# IO2.net
KiCad netlist of a schematic drawn in Altium Designer
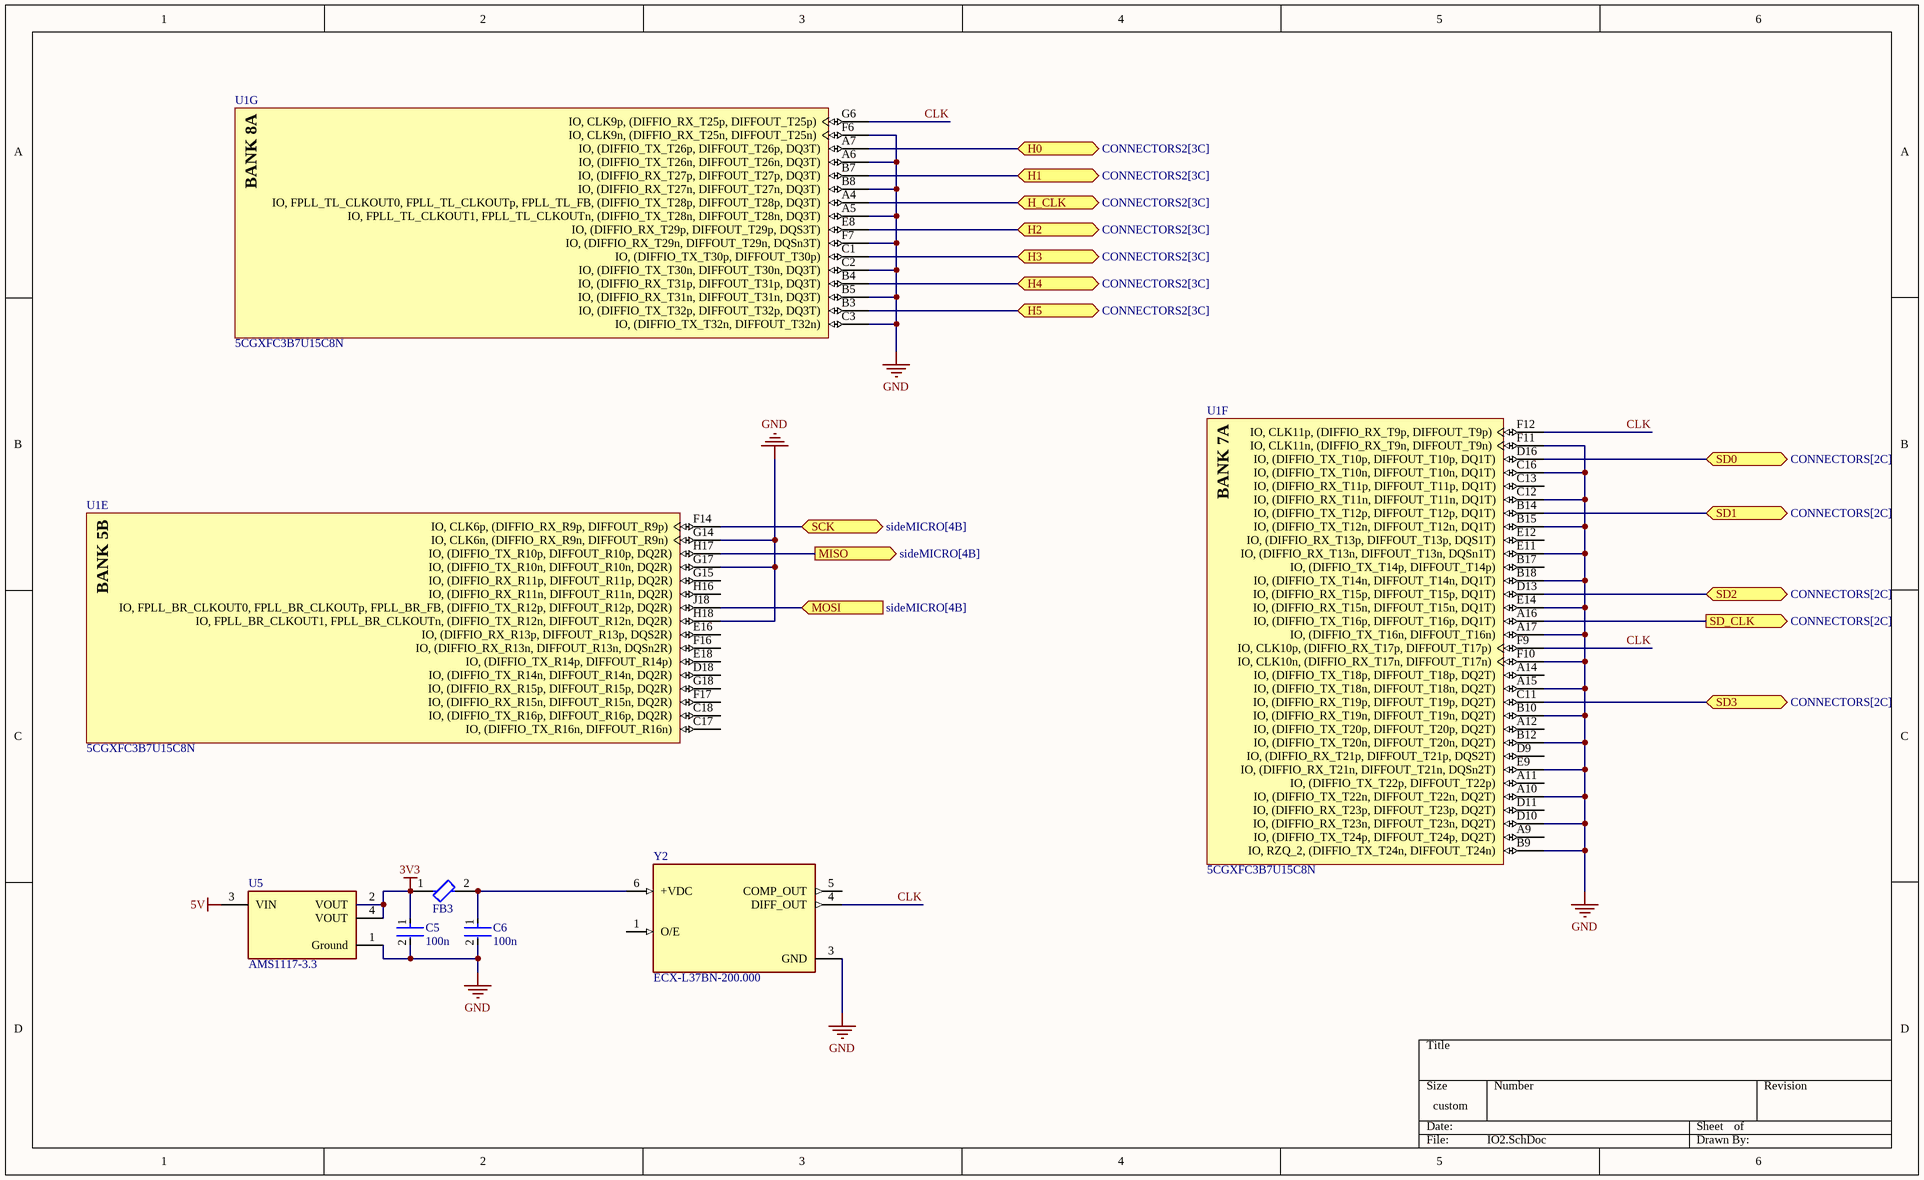
[diagram p0: IO2.SchDoc]

(export (version "E")
  (design (tool "Eeschema 10.0.6"))
  (components
    (comp (ref "C5")
      (value "100n")
      (footprint "FP-CL10-IPC_C")
      (description "Cap Ceramic 4.7uF 10V X5R ±10% Pad SMD 0603 +85°C T/R")
      (fields (field (name "TOLERANCE") "10%"))
      (libsource (lib "Altium Content Vault") (part "b4654b650e69147ec39a6b967a45e02"))
    )
    (comp (ref "C6")
      (value "100n")
      (footprint "FP-CL10-IPC_C")
      (description "Cap Ceramic 4.7uF 10V X5R ±10% Pad SMD 0603 +85°C T/R")
      (fields (field (name "TOLERANCE") "10%"))
      (libsource (lib "Altium Content Vault") (part "b4654b650e69147ec39a6b967a45e02"))
    )
    (comp (ref "FB3")
      (value "BLM18KG121TN1D")
      (footprint "FP-BLM18-0_15-t0_6-d1_2-IPC_A")
      (description "FERRITE BEAD 120 OHM 0603 1LN")
      (fields (field (name "TOLERANCE") "25%"))
      (libsource (lib "Altium Content Vault") (part "5f30dd21d616792df468990f7003faa"))
    )
    (comp (ref "U1")
      (value "5CGXFC3B7U15C8N")
      (footprint "ALTR-UBGA324_A-150")
      (fields (field (name "MANUFACTURER") "Altera"))
      (libsource (lib "Altium Content Vault") (part "ALTR-5CGXFC3B6U15"))
    )
    (comp (ref "U5")
      (value "AMS1117-3.3")
      (footprint "FP-AMS1117-IPC_C")
      (description "LDO Voltage Regulators 1A, 3.3V")
      (fields
        (field (name "OCTOPART") "https://octopart.com/ams1117-3.3-advanced+monolithic+systems-25899300")
        (field (name "MANUFACTURER") "Advanced Monolithic Systems")
      )
      (libsource (lib "Altium Content Vault") (part "8bdbb5f8e77002000e30dd2845d0354"))
    )
    (comp (ref "Y2")
      (value "ECX-L37BN-200.000")
      (footprint "OSC_ECX-L37BN-200.000")
      (description "200 MHz XO (Standard) LVDS Oscillator 3.3V Enable/Disable 6-SMD, No Lead")
      (fields (field (name "MF") "ECS Inc."))
      (libsource (lib "ECX-L37BN-200.000") (part "ECX-L37BN-200.000"))
    )
  )
  (nets
    (net (code "1") (name "/CLK") (class "Default")
      (node (ref "U1") (pin "F12") (pinfunction "IO,_CLK11p,_(DIFFIO_RX_T9p,_DIFFOUT_T9p)_F12") (pintype "bidirectional"))
      (node (ref "U1") (pin "F9") (pinfunction "IO,_CLK10p,_(DIFFIO_RX_T17p,_DIFFOUT_T17p)_F9") (pintype "bidirectional"))
      (node (ref "U1") (pin "G6") (pinfunction "IO,_CLK9p,_(DIFFIO_RX_T25p,_DIFFOUT_T25p)_G6") (pintype "bidirectional"))
      (node (ref "Y2") (pin "4") (pinfunction "DIFF_OUT_4") (pintype "output"))
    )
    (net (code "2") (name "/H0") (class "Default")
      (node (ref "U1") (pin "A7") (pinfunction "IO,_(DIFFIO_TX_T26p,_DIFFOUT_T26p,_DQ3T)_A7") (pintype "bidirectional"))
    )
    (net (code "3") (name "/H1") (class "Default")
      (node (ref "U1") (pin "B7") (pinfunction "IO,_(DIFFIO_RX_T27p,_DIFFOUT_T27p,_DQ3T)_B7") (pintype "bidirectional"))
    )
    (net (code "4") (name "/H2") (class "Default")
      (node (ref "U1") (pin "E8") (pinfunction "IO,_(DIFFIO_RX_T29p,_DIFFOUT_T29p,_DQS3T)_E8") (pintype "bidirectional"))
    )
    (net (code "5") (name "/H3") (class "Default")
      (node (ref "U1") (pin "C1") (pinfunction "IO,_(DIFFIO_TX_T30p,_DIFFOUT_T30p)_C1") (pintype "bidirectional"))
    )
    (net (code "6") (name "/H4") (class "Default")
      (node (ref "U1") (pin "B4") (pinfunction "IO,_(DIFFIO_RX_T31p,_DIFFOUT_T31p,_DQ3T)_B4") (pintype "bidirectional"))
    )
    (net (code "7") (name "/H5") (class "Default")
      (node (ref "U1") (pin "B3") (pinfunction "IO,_(DIFFIO_TX_T32p,_DIFFOUT_T32p,_DQ3T)_B3") (pintype "bidirectional"))
    )
    (net (code "8") (name "/H_CLK") (class "Default")
      (node (ref "U1") (pin "A4") (pinfunction "IO,_FPLL_TL_CLKOUT0,_FPLL_TL_CLKOUTp,_FPLL_TL_FB,_(DIFFIO_TX_T28p,_DIFFOUT_T28p,_DQ3T)_A4") (pintype "bidirectional"))
    )
    (net (code "9") (name "/MISO") (class "Default")
      (node (ref "U1") (pin "H17") (pinfunction "IO,_(DIFFIO_TX_R10p,_DIFFOUT_R10p,_DQ2R)_H17") (pintype "bidirectional"))
    )
    (net (code "10") (name "/MOSI") (class "Default")
      (node (ref "U1") (pin "J18") (pinfunction "IO,_FPLL_BR_CLKOUT0,_FPLL_BR_CLKOUTp,_FPLL_BR_FB,_(DIFFIO_TX_R12p,_DIFFOUT_R12p,_DQ2R)_J18") (pintype "bidirectional"))
    )
    (net (code "11") (name "/SCK") (class "Default")
      (node (ref "U1") (pin "F14") (pinfunction "IO,_CLK6p,_(DIFFIO_RX_R9p,_DIFFOUT_R9p)_F14") (pintype "bidirectional"))
    )
    (net (code "12") (name "/SD0") (class "Default")
      (node (ref "U1") (pin "D16") (pinfunction "IO,_(DIFFIO_TX_T10p,_DIFFOUT_T10p,_DQ1T)_D16") (pintype "bidirectional"))
    )
    (net (code "13") (name "/SD1") (class "Default")
      (node (ref "U1") (pin "B14") (pinfunction "IO,_(DIFFIO_TX_T12p,_DIFFOUT_T12p,_DQ1T)_B14") (pintype "bidirectional"))
    )
    (net (code "14") (name "/SD2") (class "Default")
      (node (ref "U1") (pin "D13") (pinfunction "IO,_(DIFFIO_RX_T15p,_DIFFOUT_T15p,_DQ1T)_D13") (pintype "bidirectional"))
    )
    (net (code "15") (name "/SD3") (class "Default")
      (node (ref "U1") (pin "C11") (pinfunction "IO,_(DIFFIO_RX_T19p,_DIFFOUT_T19p,_DQ2T)_C11") (pintype "bidirectional"))
    )
    (net (code "16") (name "/SD_CLK") (class "Default")
      (node (ref "U1") (pin "A16") (pinfunction "IO,_(DIFFIO_TX_T16p,_DIFFOUT_T16p,_DQ1T)_A16") (pintype "bidirectional"))
    )
    (net (code "17") (name "3V3") (class "Default")
      (node (ref "C5") (pin "1") (pinfunction "1_1") (pintype "passive"))
      (node (ref "FB3") (pin "1") (pinfunction "1_1") (pintype "passive"))
      (node (ref "U5") (pin "2") (pinfunction "VOUT_2") (pintype "passive"))
      (node (ref "U5") (pin "4") (pinfunction "VOUT_4") (pintype "passive"))
    )
    (net (code "18") (name "5V") (class "Default")
      (node (ref "U5") (pin "3") (pinfunction "VIN_3") (pintype "power_in"))
    )
    (net (code "19") (name "GND") (class "Default")
      (node (ref "C5") (pin "2") (pinfunction "2_2") (pintype "passive"))
      (node (ref "C6") (pin "2") (pinfunction "2_2") (pintype "passive"))
      (node (ref "U1") (pin "A10") (pinfunction "IO,_(DIFFIO_TX_T22n,_DIFFOUT_T22n,_DQ2T)_A10") (pintype "bidirectional"))
      (node (ref "U1") (pin "A15") (pinfunction "IO,_(DIFFIO_TX_T18n,_DIFFOUT_T18n,_DQ2T)_A15") (pintype "bidirectional"))
      (node (ref "U1") (pin "A17") (pinfunction "IO,_(DIFFIO_TX_T16n,_DIFFOUT_T16n)_A17") (pintype "bidirectional"))
      (node (ref "U1") (pin "A5") (pinfunction "IO,_FPLL_TL_CLKOUT1,_FPLL_TL_CLKOUTn,_(DIFFIO_TX_T28n,_DIFFOUT_T28n,_DQ3T)_A5") (pintype "bidirectional"))
      (node (ref "U1") (pin "A6") (pinfunction "IO,_(DIFFIO_TX_T26n,_DIFFOUT_T26n,_DQ3T)_A6") (pintype "bidirectional"))
      (node (ref "U1") (pin "B10") (pinfunction "IO,_(DIFFIO_RX_T19n,_DIFFOUT_T19n,_DQ2T)_B10") (pintype "bidirectional"))
      (node (ref "U1") (pin "B12") (pinfunction "IO,_(DIFFIO_TX_T20n,_DIFFOUT_T20n,_DQ2T)_B12") (pintype "bidirectional"))
      (node (ref "U1") (pin "B15") (pinfunction "IO,_(DIFFIO_TX_T12n,_DIFFOUT_T12n,_DQ1T)_B15") (pintype "bidirectional"))
      (node (ref "U1") (pin "B18") (pinfunction "IO,_(DIFFIO_TX_T14n,_DIFFOUT_T14n,_DQ1T)_B18") (pintype "bidirectional"))
      (node (ref "U1") (pin "B5") (pinfunction "IO,_(DIFFIO_RX_T31n,_DIFFOUT_T31n,_DQ3T)_B5") (pintype "bidirectional"))
      (node (ref "U1") (pin "B8") (pinfunction "IO,_(DIFFIO_RX_T27n,_DIFFOUT_T27n,_DQ3T)_B8") (pintype "bidirectional"))
      (node (ref "U1") (pin "B9") (pinfunction "IO,_RZQ_2,_(DIFFIO_TX_T24n,_DIFFOUT_T24n)_B9") (pintype "bidirectional"))
      (node (ref "U1") (pin "C12") (pinfunction "IO,_(DIFFIO_RX_T11n,_DIFFOUT_T11n,_DQ1T)_C12") (pintype "bidirectional"))
      (node (ref "U1") (pin "C16") (pinfunction "IO,_(DIFFIO_TX_T10n,_DIFFOUT_T10n,_DQ1T)_C16") (pintype "bidirectional"))
      (node (ref "U1") (pin "C2") (pinfunction "IO,_(DIFFIO_TX_T30n,_DIFFOUT_T30n,_DQ3T)_C2") (pintype "bidirectional"))
      (node (ref "U1") (pin "C3") (pinfunction "IO,_(DIFFIO_TX_T32n,_DIFFOUT_T32n)_C3") (pintype "bidirectional"))
      (node (ref "U1") (pin "D10") (pinfunction "IO,_(DIFFIO_RX_T23n,_DIFFOUT_T23n,_DQ2T)_D10") (pintype "bidirectional"))
      (node (ref "U1") (pin "E11") (pinfunction "IO,_(DIFFIO_RX_T13n,_DIFFOUT_T13n,_DQSn1T)_E11") (pintype "bidirectional"))
      (node (ref "U1") (pin "E14") (pinfunction "IO,_(DIFFIO_RX_T15n,_DIFFOUT_T15n,_DQ1T)_E14") (pintype "bidirectional"))
      (node (ref "U1") (pin "E9") (pinfunction "IO,_(DIFFIO_RX_T21n,_DIFFOUT_T21n,_DQSn2T)_E9") (pintype "bidirectional"))
      (node (ref "U1") (pin "F10") (pinfunction "IO,_CLK10n,_(DIFFIO_RX_T17n,_DIFFOUT_T17n)_F10") (pintype "bidirectional"))
      (node (ref "U1") (pin "F11") (pinfunction "IO,_CLK11n,_(DIFFIO_RX_T9n,_DIFFOUT_T9n)_F11") (pintype "bidirectional"))
      (node (ref "U1") (pin "F6") (pinfunction "IO,_CLK9n,_(DIFFIO_RX_T25n,_DIFFOUT_T25n)_F6") (pintype "bidirectional"))
      (node (ref "U1") (pin "F7") (pinfunction "IO,_(DIFFIO_RX_T29n,_DIFFOUT_T29n,_DQSn3T)_F7") (pintype "bidirectional"))
      (node (ref "U1") (pin "G14") (pinfunction "IO,_CLK6n,_(DIFFIO_RX_R9n,_DIFFOUT_R9n)_G14") (pintype "bidirectional"))
      (node (ref "U1") (pin "G17") (pinfunction "IO,_(DIFFIO_TX_R10n,_DIFFOUT_R10n,_DQ2R)_G17") (pintype "bidirectional"))
      (node (ref "U1") (pin "H18") (pinfunction "IO,_FPLL_BR_CLKOUT1,_FPLL_BR_CLKOUTn,_(DIFFIO_TX_R12n,_DIFFOUT_R12n,_DQ2R)_H18") (pintype "bidirectional"))
      (node (ref "U5") (pin "1") (pinfunction "Ground_1") (pintype "power_in"))
      (node (ref "Y2") (pin "3") (pinfunction "GND_3") (pintype "power_in"))
    )
    (net (code "20") (name "Net-(Y2-+VDC)") (class "Default")
      (node (ref "C6") (pin "1") (pinfunction "1_1") (pintype "passive"))
      (node (ref "FB3") (pin "2") (pinfunction "2_2") (pintype "passive"))
      (node (ref "Y2") (pin "6") (pinfunction "+VDC_6") (pintype "input"))
    )
    (net (code "21") (name "unconnected-(U1E-IO,_(DIFFIO_RX_R11n,_DIFFOUT_R11n,_DQ2R)-PadH16)") (class "Default")
      (node (ref "U1") (pin "H16") (pinfunction "IO,_(DIFFIO_RX_R11n,_DIFFOUT_R11n,_DQ2R)_H16") (pintype "bidirectional"))
    )
    (net (code "22") (name "unconnected-(U1E-IO,_(DIFFIO_RX_R11p,_DIFFOUT_R11p,_DQ2R)-PadG15)") (class "Default")
      (node (ref "U1") (pin "G15") (pinfunction "IO,_(DIFFIO_RX_R11p,_DIFFOUT_R11p,_DQ2R)_G15") (pintype "bidirectional"))
    )
    (net (code "23") (name "unconnected-(U1E-IO,_(DIFFIO_RX_R13n,_DIFFOUT_R13n,_DQSn2R)-PadF16)") (class "Default")
      (node (ref "U1") (pin "F16") (pinfunction "IO,_(DIFFIO_RX_R13n,_DIFFOUT_R13n,_DQSn2R)_F16") (pintype "bidirectional"))
    )
    (net (code "24") (name "unconnected-(U1E-IO,_(DIFFIO_RX_R13p,_DIFFOUT_R13p,_DQS2R)-PadE16)") (class "Default")
      (node (ref "U1") (pin "E16") (pinfunction "IO,_(DIFFIO_RX_R13p,_DIFFOUT_R13p,_DQS2R)_E16") (pintype "bidirectional"))
    )
    (net (code "25") (name "unconnected-(U1E-IO,_(DIFFIO_RX_R15n,_DIFFOUT_R15n,_DQ2R)-PadF17)") (class "Default")
      (node (ref "U1") (pin "F17") (pinfunction "IO,_(DIFFIO_RX_R15n,_DIFFOUT_R15n,_DQ2R)_F17") (pintype "bidirectional"))
    )
    (net (code "26") (name "unconnected-(U1E-IO,_(DIFFIO_RX_R15p,_DIFFOUT_R15p,_DQ2R)-PadG18)") (class "Default")
      (node (ref "U1") (pin "G18") (pinfunction "IO,_(DIFFIO_RX_R15p,_DIFFOUT_R15p,_DQ2R)_G18") (pintype "bidirectional"))
    )
    (net (code "27") (name "unconnected-(U1E-IO,_(DIFFIO_TX_R14n,_DIFFOUT_R14n,_DQ2R)-PadD18)") (class "Default")
      (node (ref "U1") (pin "D18") (pinfunction "IO,_(DIFFIO_TX_R14n,_DIFFOUT_R14n,_DQ2R)_D18") (pintype "bidirectional"))
    )
    (net (code "28") (name "unconnected-(U1E-IO,_(DIFFIO_TX_R14p,_DIFFOUT_R14p)-PadE18)") (class "Default")
      (node (ref "U1") (pin "E18") (pinfunction "IO,_(DIFFIO_TX_R14p,_DIFFOUT_R14p)_E18") (pintype "bidirectional"))
    )
    (net (code "29") (name "unconnected-(U1E-IO,_(DIFFIO_TX_R16n,_DIFFOUT_R16n)-PadC17)") (class "Default")
      (node (ref "U1") (pin "C17") (pinfunction "IO,_(DIFFIO_TX_R16n,_DIFFOUT_R16n)_C17") (pintype "bidirectional"))
    )
    (net (code "30") (name "unconnected-(U1E-IO,_(DIFFIO_TX_R16p,_DIFFOUT_R16p,_DQ2R)-PadC18)") (class "Default")
      (node (ref "U1") (pin "C18") (pinfunction "IO,_(DIFFIO_TX_R16p,_DIFFOUT_R16p,_DQ2R)_C18") (pintype "bidirectional"))
    )
    (net (code "31") (name "unconnected-(U1F-IO,_(DIFFIO_RX_T11p,_DIFFOUT_T11p,_DQ1T)-PadC13)") (class "Default")
      (node (ref "U1") (pin "C13") (pinfunction "IO,_(DIFFIO_RX_T11p,_DIFFOUT_T11p,_DQ1T)_C13") (pintype "bidirectional"))
    )
    (net (code "32") (name "unconnected-(U1F-IO,_(DIFFIO_RX_T13p,_DIFFOUT_T13p,_DQS1T)-PadE12)") (class "Default")
      (node (ref "U1") (pin "E12") (pinfunction "IO,_(DIFFIO_RX_T13p,_DIFFOUT_T13p,_DQS1T)_E12") (pintype "bidirectional"))
    )
    (net (code "33") (name "unconnected-(U1F-IO,_(DIFFIO_RX_T21p,_DIFFOUT_T21p,_DQS2T)-PadD9)") (class "Default")
      (node (ref "U1") (pin "D9") (pinfunction "IO,_(DIFFIO_RX_T21p,_DIFFOUT_T21p,_DQS2T)_D9") (pintype "bidirectional"))
    )
    (net (code "34") (name "unconnected-(U1F-IO,_(DIFFIO_RX_T23p,_DIFFOUT_T23p,_DQ2T)-PadD11)") (class "Default")
      (node (ref "U1") (pin "D11") (pinfunction "IO,_(DIFFIO_RX_T23p,_DIFFOUT_T23p,_DQ2T)_D11") (pintype "bidirectional"))
    )
    (net (code "35") (name "unconnected-(U1F-IO,_(DIFFIO_TX_T14p,_DIFFOUT_T14p)-PadB17)") (class "Default")
      (node (ref "U1") (pin "B17") (pinfunction "IO,_(DIFFIO_TX_T14p,_DIFFOUT_T14p)_B17") (pintype "bidirectional"))
    )
    (net (code "36") (name "unconnected-(U1F-IO,_(DIFFIO_TX_T18p,_DIFFOUT_T18p,_DQ2T)-PadA14)") (class "Default")
      (node (ref "U1") (pin "A14") (pinfunction "IO,_(DIFFIO_TX_T18p,_DIFFOUT_T18p,_DQ2T)_A14") (pintype "bidirectional"))
    )
    (net (code "37") (name "unconnected-(U1F-IO,_(DIFFIO_TX_T20p,_DIFFOUT_T20p,_DQ2T)-PadA12)") (class "Default")
      (node (ref "U1") (pin "A12") (pinfunction "IO,_(DIFFIO_TX_T20p,_DIFFOUT_T20p,_DQ2T)_A12") (pintype "bidirectional"))
    )
    (net (code "38") (name "unconnected-(U1F-IO,_(DIFFIO_TX_T22p,_DIFFOUT_T22p)-PadA11)") (class "Default")
      (node (ref "U1") (pin "A11") (pinfunction "IO,_(DIFFIO_TX_T22p,_DIFFOUT_T22p)_A11") (pintype "bidirectional"))
    )
    (net (code "39") (name "unconnected-(U1F-IO,_(DIFFIO_TX_T24p,_DIFFOUT_T24p,_DQ2T)-PadA9)") (class "Default")
      (node (ref "U1") (pin "A9") (pinfunction "IO,_(DIFFIO_TX_T24p,_DIFFOUT_T24p,_DQ2T)_A9") (pintype "bidirectional"))
    )
    (net (code "40") (name "unconnected-(Y2-COMP_OUT-Pad5)") (class "Default")
      (node (ref "Y2") (pin "5") (pinfunction "COMP_OUT_5") (pintype "output"))
    )
    (net (code "41") (name "unconnected-(Y2-O{slash}E-Pad1)") (class "Default")
      (node (ref "Y2") (pin "1") (pinfunction "O/E_1") (pintype "input"))
    )
  )
)
